# BusDistribution.net
KiCad netlist of a schematic drawn in Altium Designer
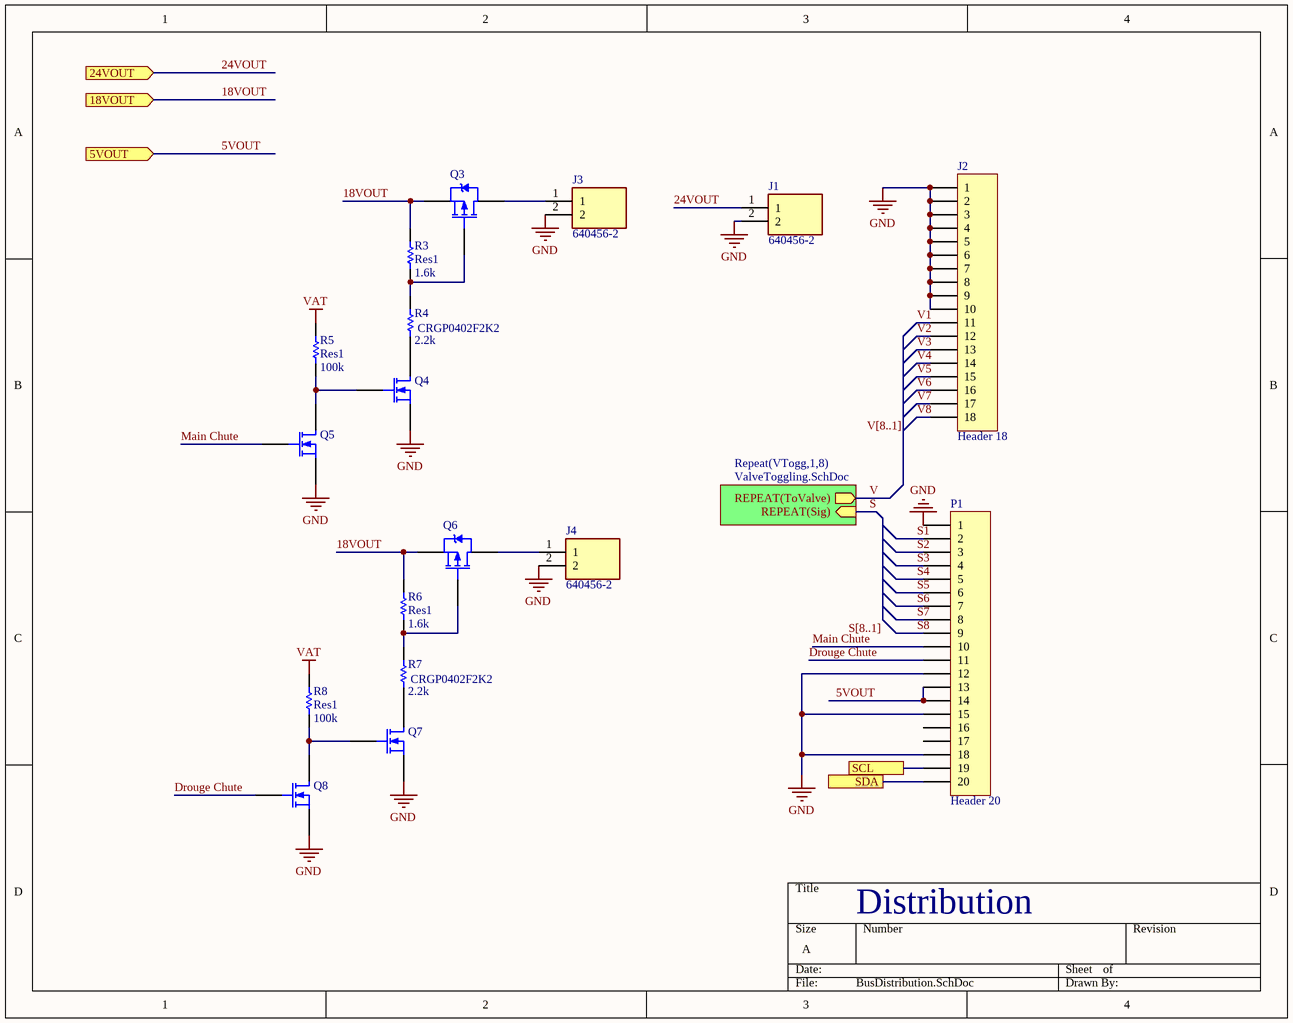
[diagram p0: BusDistribution.SchDoc]

(export (version "E")
  (design (tool "Eeschema 10.0.6"))
  (components
    (comp (ref "J1")
      (value "640456-2")
      (footprint "16404562")
      (description "Connector")
      (fields (field (name "MOUSER PART NUMBER") "571-6404562") (field (name "RS PART NUMBER") "1320355P"))
      (libsource (lib "*") (part "640456-2"))
    )
    (comp (ref "J2")
      (value "Header 18")
      (footprint "15247182")
      (description "Header, 18-Pin")
      (fields (field (name "PUBLISHER") "Altium Limited"))
      (libsource (lib "Miscellaneous Connectors") (part "Header 18"))
    )
    (comp (ref "J3")
      (value "640456-2")
      (footprint "16404562")
      (description "Connector")
      (fields (field (name "MOUSER PART NUMBER") "571-6404562") (field (name "RS PART NUMBER") "1320355P"))
      (libsource (lib "*") (part "640456-2"))
    )
    (comp (ref "J4")
      (value "640456-2")
      (footprint "16404562")
      (description "Connector")
      (fields (field (name "MOUSER PART NUMBER") "571-6404562") (field (name "RS PART NUMBER") "1320355P"))
      (libsource (lib "*") (part "640456-2"))
    )
    (comp (ref "P1")
      (value "Header 20")
      (footprint "HDR1X20")
      (description "Header, 20-Pin")
      (fields (field (name "PUBLISHER") "Altium Limited"))
      (libsource (lib "Miscellaneous Connectors") (part "Header 20"))
    )
    (comp (ref "Q3")
      (value "MED power PMOS")
      (footprint "SOT23_L")
      (description "P-Channel Power MOSFET")
      (fields (field (name "PUBLISHER") "Altium Limited"))
      (libsource (lib "Miscellaneous Devices") (part "PMOS-2"))
    )
    (comp (ref "Q4")
      (value "Low Power NMOS")
      (footprint "SOT23_L")
      (description "N-Channel MOSFET")
      (fields (field (name "PUBLISHER") "Altium Limited"))
      (libsource (lib "Miscellaneous Devices") (part "MOSFET-N"))
    )
    (comp (ref "Q5")
      (value "Low power NMOS")
      (footprint "SOT23_L")
      (description "N-Channel MOSFET")
      (fields (field (name "PUBLISHER") "Altium Limited"))
      (libsource (lib "Miscellaneous Devices") (part "MOSFET-N"))
    )
    (comp (ref "Q6")
      (value "MED power PMOS")
      (footprint "SOT23_L")
      (description "P-Channel Power MOSFET")
      (fields (field (name "PUBLISHER") "Altium Limited"))
      (libsource (lib "Miscellaneous Devices") (part "PMOS-2"))
    )
    (comp (ref "Q7")
      (value "Low Power NMOS")
      (footprint "SOT23_L")
      (description "N-Channel MOSFET")
      (fields (field (name "PUBLISHER") "Altium Limited"))
      (libsource (lib "Miscellaneous Devices") (part "MOSFET-N"))
    )
    (comp (ref "Q8")
      (value "Low Power NMOS")
      (footprint "SOT23_L")
      (description "N-Channel MOSFET")
      (fields (field (name "PUBLISHER") "Altium Limited"))
      (libsource (lib "Miscellaneous Devices") (part "MOSFET-N"))
    )
    (comp (ref "R3")
      (value "Res1")
      (footprint "0402")
      (description "Resistor")
      (fields (field (name "ALTIUM_VALUE") "1.6k") (field (name "PUBLISHER") "Altium Limited"))
      (libsource (lib "Miscellaneous Devices") (part "Res1"))
    )
    (comp (ref "R4")
      (value "CRGP0402F2K2")
      (footprint "0402")
      (description "2.2 kOhms ±1% 0.125W, 1/8W Chip Resistor 0402 (1005 Metric) Pulse Withstanding Thick Film")
      (fields (field (name "ALTIUM_VALUE") "2.2k") (field (name "MFG") "TE Connectivity Passive Product"))
      (libsource (lib "Miscellaneous Devices") (part "Res1"))
    )
    (comp (ref "R5")
      (value "Res1")
      (footprint "0402")
      (description "Resistor")
      (fields (field (name "ALTIUM_VALUE") "100k") (field (name "PUBLISHER") "Altium Limited"))
      (libsource (lib "Miscellaneous Devices") (part "Res1"))
    )
    (comp (ref "R6")
      (value "Res1")
      (footprint "0402")
      (description "Resistor")
      (fields (field (name "ALTIUM_VALUE") "1.6k") (field (name "PUBLISHER") "Altium Limited"))
      (libsource (lib "Miscellaneous Devices") (part "Res1"))
    )
    (comp (ref "R7")
      (value "CRGP0402F2K2")
      (footprint "0402")
      (description "2.2 kOhms ±1% 0.125W, 1/8W Chip Resistor 0402 (1005 Metric) Pulse Withstanding Thick Film")
      (fields (field (name "ALTIUM_VALUE") "2.2k") (field (name "MFG") "TE Connectivity Passive Product"))
      (libsource (lib "Miscellaneous Devices") (part "Res1"))
    )
    (comp (ref "R8")
      (value "Res1")
      (footprint "0402")
      (description "Resistor")
      (fields (field (name "ALTIUM_VALUE") "100k") (field (name "PUBLISHER") "Altium Limited"))
      (libsource (lib "Miscellaneous Devices") (part "Res1"))
    )
  )
  (nets
    (net (code "1") (name "/5VOUT") (class "Default")
      (node (ref "P1") (pin "13") (pinfunction "13_13") (pintype "passive"))
      (node (ref "P1") (pin "14") (pinfunction "14_14") (pintype "passive"))
    )
    (net (code "2") (name "/18VOUT") (class "Default")
      (node (ref "Q3") (pin "3") (pinfunction "S_3") (pintype "passive"))
      (node (ref "Q6") (pin "3") (pinfunction "S_3") (pintype "passive"))
      (node (ref "R3") (pin "2") (pinfunction "2_2") (pintype "passive"))
      (node (ref "R6") (pin "2") (pinfunction "2_2") (pintype "passive"))
    )
    (net (code "3") (name "/24VOUT") (class "Default")
      (node (ref "J1") (pin "1") (pinfunction "1_1") (pintype "passive"))
    )
    (net (code "4") (name "/Drouge Chute") (class "Default")
      (node (ref "P1") (pin "11") (pinfunction "11_11") (pintype "passive"))
      (node (ref "Q8") (pin "2") (pinfunction "G_2") (pintype "passive"))
    )
    (net (code "5") (name "/Main Chute") (class "Default")
      (node (ref "P1") (pin "10") (pinfunction "10_10") (pintype "passive"))
      (node (ref "Q5") (pin "2") (pinfunction "G_2") (pintype "passive"))
    )
    (net (code "7") (name "/S1") (class "Default")
      (node (ref "P1") (pin "2") (pinfunction "2_2") (pintype "passive"))
    )
    (net (code "8") (name "/S2") (class "Default")
      (node (ref "P1") (pin "3") (pinfunction "3_3") (pintype "passive"))
    )
    (net (code "9") (name "/S3") (class "Default")
      (node (ref "P1") (pin "4") (pinfunction "4_4") (pintype "passive"))
    )
    (net (code "10") (name "/S4") (class "Default")
      (node (ref "P1") (pin "5") (pinfunction "5_5") (pintype "passive"))
    )
    (net (code "11") (name "/S5") (class "Default")
      (node (ref "P1") (pin "6") (pinfunction "6_6") (pintype "passive"))
    )
    (net (code "12") (name "/S6") (class "Default")
      (node (ref "P1") (pin "7") (pinfunction "7_7") (pintype "passive"))
    )
    (net (code "13") (name "/S7") (class "Default")
      (node (ref "P1") (pin "8") (pinfunction "8_8") (pintype "passive"))
    )
    (net (code "14") (name "/S8") (class "Default")
      (node (ref "P1") (pin "9") (pinfunction "9_9") (pintype "passive"))
    )
    (net (code "15") (name "/SCL") (class "Default")
      (node (ref "P1") (pin "19") (pinfunction "19_19") (pintype "passive"))
    )
    (net (code "16") (name "/SDA") (class "Default")
      (node (ref "P1") (pin "20") (pinfunction "20_20") (pintype "passive"))
    )
    (net (code "19") (name "/V1") (class "Default")
      (node (ref "J2") (pin "11") (pinfunction "11_11") (pintype "passive"))
    )
    (net (code "20") (name "/V2") (class "Default")
      (node (ref "J2") (pin "12") (pinfunction "12_12") (pintype "passive"))
    )
    (net (code "21") (name "/V3") (class "Default")
      (node (ref "J2") (pin "13") (pinfunction "13_13") (pintype "passive"))
    )
    (net (code "22") (name "/V4") (class "Default")
      (node (ref "J2") (pin "14") (pinfunction "14_14") (pintype "passive"))
    )
    (net (code "23") (name "/V5") (class "Default")
      (node (ref "J2") (pin "15") (pinfunction "15_15") (pintype "passive"))
    )
    (net (code "24") (name "/V6") (class "Default")
      (node (ref "J2") (pin "16") (pinfunction "16_16") (pintype "passive"))
    )
    (net (code "25") (name "/V7") (class "Default")
      (node (ref "J2") (pin "17") (pinfunction "17_17") (pintype "passive"))
    )
    (net (code "26") (name "/V8") (class "Default")
      (node (ref "J2") (pin "18") (pinfunction "18_18") (pintype "passive"))
    )
    (net (code "28") (name "GND") (class "Default")
      (node (ref "J1") (pin "2") (pinfunction "2_2") (pintype "passive"))
      (node (ref "J2") (pin "1") (pinfunction "1_1") (pintype "passive"))
      (node (ref "J2") (pin "10") (pinfunction "10_10") (pintype "passive"))
      (node (ref "J2") (pin "2") (pinfunction "2_2") (pintype "passive"))
      (node (ref "J2") (pin "3") (pinfunction "3_3") (pintype "passive"))
      (node (ref "J2") (pin "4") (pinfunction "4_4") (pintype "passive"))
      (node (ref "J2") (pin "5") (pinfunction "5_5") (pintype "passive"))
      (node (ref "J2") (pin "6") (pinfunction "6_6") (pintype "passive"))
      (node (ref "J2") (pin "7") (pinfunction "7_7") (pintype "passive"))
      (node (ref "J2") (pin "8") (pinfunction "8_8") (pintype "passive"))
      (node (ref "J2") (pin "9") (pinfunction "9_9") (pintype "passive"))
      (node (ref "J3") (pin "2") (pinfunction "2_2") (pintype "passive"))
      (node (ref "J4") (pin "2") (pinfunction "2_2") (pintype "passive"))
      (node (ref "P1") (pin "1") (pinfunction "1_1") (pintype "passive"))
      (node (ref "P1") (pin "12") (pinfunction "12_12") (pintype "passive"))
      (node (ref "P1") (pin "15") (pinfunction "15_15") (pintype "passive"))
      (node (ref "P1") (pin "18") (pinfunction "18_18") (pintype "passive"))
      (node (ref "Q4") (pin "3") (pinfunction "S_3") (pintype "passive"))
      (node (ref "Q5") (pin "3") (pinfunction "S_3") (pintype "passive"))
      (node (ref "Q7") (pin "3") (pinfunction "S_3") (pintype "passive"))
      (node (ref "Q8") (pin "3") (pinfunction "S_3") (pintype "passive"))
    )
    (net (code "29") (name "Net-(Q3-D)") (class "Default")
      (node (ref "J3") (pin "1") (pinfunction "1_1") (pintype "passive"))
      (node (ref "Q3") (pin "2") (pinfunction "D_2") (pintype "passive"))
    )
    (net (code "30") (name "Net-(Q3-G)") (class "Default")
      (node (ref "Q3") (pin "1") (pinfunction "G_1") (pintype "passive"))
      (node (ref "R3") (pin "1") (pinfunction "1_1") (pintype "passive"))
      (node (ref "R4") (pin "2") (pinfunction "2_2") (pintype "passive"))
    )
    (net (code "31") (name "Net-(Q4-D)") (class "Default")
      (node (ref "Q4") (pin "1") (pinfunction "D_1") (pintype "passive"))
      (node (ref "R4") (pin "1") (pinfunction "1_1") (pintype "passive"))
    )
    (net (code "32") (name "Net-(Q4-G)") (class "Default")
      (node (ref "Q4") (pin "2") (pinfunction "G_2") (pintype "passive"))
      (node (ref "Q5") (pin "1") (pinfunction "D_1") (pintype "passive"))
      (node (ref "R5") (pin "1") (pinfunction "1_1") (pintype "passive"))
    )
    (net (code "33") (name "Net-(Q6-D)") (class "Default")
      (node (ref "J4") (pin "1") (pinfunction "1_1") (pintype "passive"))
      (node (ref "Q6") (pin "2") (pinfunction "D_2") (pintype "passive"))
    )
    (net (code "34") (name "Net-(Q6-G)") (class "Default")
      (node (ref "Q6") (pin "1") (pinfunction "G_1") (pintype "passive"))
      (node (ref "R6") (pin "1") (pinfunction "1_1") (pintype "passive"))
      (node (ref "R7") (pin "2") (pinfunction "2_2") (pintype "passive"))
    )
    (net (code "35") (name "Net-(Q7-D)") (class "Default")
      (node (ref "Q7") (pin "1") (pinfunction "D_1") (pintype "passive"))
      (node (ref "R7") (pin "1") (pinfunction "1_1") (pintype "passive"))
    )
    (net (code "36") (name "Net-(Q7-G)") (class "Default")
      (node (ref "Q7") (pin "2") (pinfunction "G_2") (pintype "passive"))
      (node (ref "Q8") (pin "1") (pinfunction "D_1") (pintype "passive"))
      (node (ref "R8") (pin "1") (pinfunction "1_1") (pintype "passive"))
    )
    (net (code "37") (name "VAT") (class "Default")
      (node (ref "R5") (pin "2") (pinfunction "2_2") (pintype "passive"))
      (node (ref "R8") (pin "2") (pinfunction "2_2") (pintype "passive"))
    )
    (net (code "38") (name "unconnected-(P1-Pad16)") (class "Default")
      (node (ref "P1") (pin "16") (pinfunction "16_16") (pintype "passive"))
    )
    (net (code "39") (name "unconnected-(P1-Pad17)") (class "Default")
      (node (ref "P1") (pin "17") (pinfunction "17_17") (pintype "passive"))
    )
  )
)
